# 15-FPGA-01b.net
KiCad netlist of a schematic drawn in Altium Designer
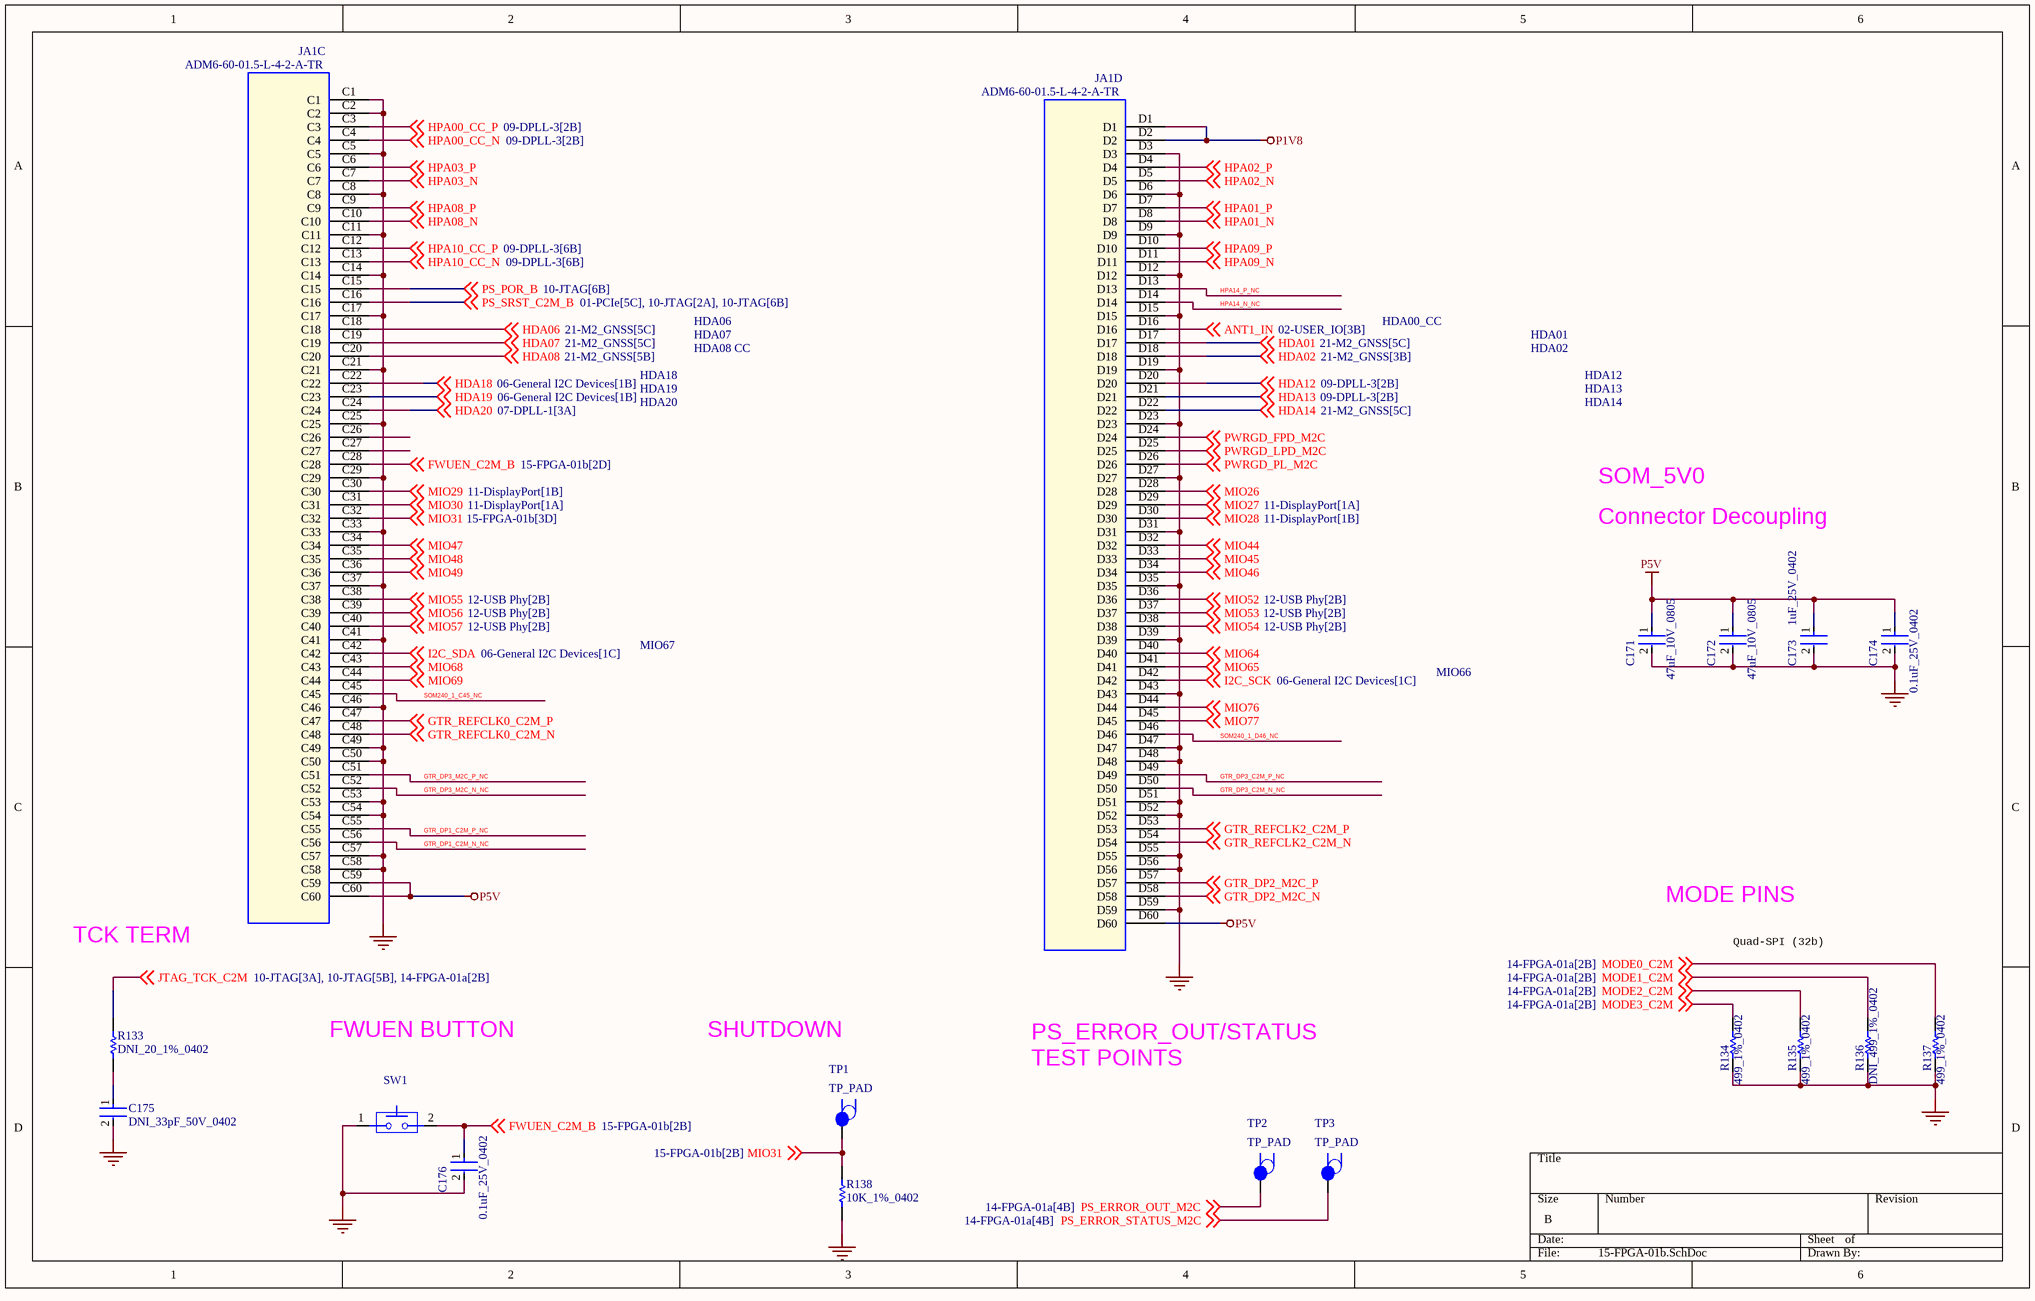
[diagram p0: 15-FPGA-01b.SchDoc]

(export (version "E")
  (design (tool "Eeschema 10.0.6"))
  (components
    (comp (ref "C171")
      (value "47uF_10V_0805")
      (footprint "FP-GRM21B-0_2-e0_2_0_7-IPC_A")
      (description "Chip Multilayer Ceramic Capacitors for General Purpose, 0805, 47uF, X5R, 15%, 20%, 10V")
      (fields (field (name "TOLERANCE") "20%") (field (name "VOLTAGE") "10V"))
      (libsource (lib "Altium Content Vault") (part "b4654b650e69147ec39a6b967a45e02"))
    )
    (comp (ref "C172")
      (value "47uF_10V_0805")
      (footprint "FP-GRM21B-0_2-e0_2_0_7-IPC_A")
      (description "Chip Multilayer Ceramic Capacitors for General Purpose, 0805, 47uF, X5R, 15%, 20%, 10V")
      (fields (field (name "TOLERANCE") "20%") (field (name "VOLTAGE") "10V"))
      (libsource (lib "Altium Content Vault") (part "b4654b650e69147ec39a6b967a45e02"))
    )
    (comp (ref "C173")
      (value "1uF_25V_0402")
      (footprint "FP-CL542-IPC_C")
      (description "Cap Ceramic 1uF 25V X5R ±10% SMD 0402 +85°C Paper T/R")
      (fields (field (name "TOLERANCE") "10%"))
      (libsource (lib "Altium Content Vault") (part "b4654b650e69147ec39a6b967a45e02"))
    )
    (comp (ref "C174")
      (value "0.1uF_25V_0402")
      (footprint "FP-0402-L_1_0_0_05-W_0_5-IPC_B")
      (description "None")
      (fields (field (name "TOLERANCE") "10%") (field (name "VOLTAGE") "25V"))
      (libsource (lib "Altium Content Vault") (part "b4654b650e69147ec39a6b967a45e02"))
    )
    (comp (ref "C175")
      (value "DNI_33pF_50V_0402")
      (footprint "FP-C1005-050-0_05-IPC_A")
      (description "Multilayer Ceramic Capacitors 33pF ±1% 50V C0G SMD 0402")
      (fields (field (name "TOLERANCE") "1%"))
      (libsource (lib "Altium Content Vault") (part "b4654b650e69147ec39a6b967a45e02"))
    )
    (comp (ref "C176")
      (value "0.1uF_25V_0402")
      (footprint "FP-0402-L_1_0_0_05-W_0_5-IPC_B")
      (description "None")
      (fields (field (name "TOLERANCE") "10%") (field (name "VOLTAGE") "25V"))
      (libsource (lib "Altium Content Vault") (part "b4654b650e69147ec39a6b967a45e02"))
    )
    (comp (ref "JA1")
      (value "ADM6-60-01.5-L-4-2-A-TR")
      (footprint "CON_SAMTEC_ADM6_60_4")
      (description "Conn Rcpt Male Vert 240 Pos 4x60 0.635mm P Black SMT")
      (fields (field (name "MANUFACTURER") "Samtec Inc.") (field (name "AGILE PART NUMBER") "CON-00383-01"))
      (libsource (lib "*") (part "SAMTEC-ADx6-60X4"))
    )
    (comp (ref "R133")
      (value "DNI_20_1%_0402")
      (footprint "RESC1005X40X25NL10T10")
      (fields
        (field (name "MANUFACTURER") "TE Connectivity / AMP")
        (field (name "PART NUMBER") "CRG0402F20R")
      )
      (libsource (lib "Altium Content Vault") (part "RES"))
    )
    (comp (ref "R134")
      (value "499_1%_0402")
      (footprint "RESC1005X40X25LL05T05")
      (fields (field (name "MANUFACTURER") "Vishay Dale") (field (name "PART NUMBER") "CRCW0402499RFKTD"))
      (libsource (lib "Altium Content Vault") (part "RES"))
    )
    (comp (ref "R135")
      (value "499_1%_0402")
      (footprint "RESC1005X40X25LL05T05")
      (fields (field (name "MANUFACTURER") "Vishay Dale") (field (name "PART NUMBER") "CRCW0402499RFKTD"))
      (libsource (lib "Altium Content Vault") (part "RES"))
    )
    (comp (ref "R136")
      (value "DNI_499_1%_0402")
      (footprint "RESC1005X40X25LL05T05")
      (fields (field (name "MANUFACTURER") "Vishay Dale") (field (name "PART NUMBER") "CRCW0402499RFKTD"))
      (libsource (lib "Altium Content Vault") (part "RES"))
    )
    (comp (ref "R137")
      (value "499_1%_0402")
      (footprint "RESC1005X40X25LL05T05")
      (fields (field (name "MANUFACTURER") "Vishay Dale") (field (name "PART NUMBER") "CRCW0402499RFKTD"))
      (libsource (lib "Altium Content Vault") (part "RES"))
    )
    (comp (ref "R138")
      (value "10K_1%_0402")
      (footprint "RESC1005X40X25ML05T05")
      (fields (field (name "PART NUMBER") "ERJ-2GEJ103X") (field (name "MANUFACTURER") "Panasonic"))
      (libsource (lib "Altium Content Vault") (part "RES"))
    )
    (comp (ref "SW1")
      (value "B3U-1000P")
      (footprint "SW_OMRON_2P")
      (description "Switch SPST-NO Mom 50mA 12V 1.6mm H 1.5Nw SMT IP40")
      (fields (field (name "MANUFACTURER") "OMRON") (field (name "AGILE PART NUMBER") "SWH-00003-01"))
      (libsource (lib "*") (part "BTN_MOMENT"))
    )
    (comp (ref "TP1")
      (value "TP_PAD")
      (footprint "TP_PAD")
      (description "TEST POINT 24mil SM pad")
      (fields (field (name "MANF") "DNP") (field (name "OWNER") "3709"))
      (libsource (lib "*") (part "TP"))
    )
    (comp (ref "TP2")
      (value "TP_PAD")
      (footprint "TP_PAD")
      (description "TEST POINT 24mil SM pad")
      (fields (field (name "MANF") "DNP") (field (name "OWNER") "3709"))
      (libsource (lib "*") (part "TP"))
    )
    (comp (ref "TP3")
      (value "TP_PAD")
      (footprint "TP_PAD")
      (description "TEST POINT 24mil SM pad")
      (fields (field (name "MANF") "DNP") (field (name "OWNER") "3709"))
      (libsource (lib "*") (part "TP"))
    )
  )
  (nets
    (net (code "1") (name "/GTR_DP1_C2M_N_NC") (class "Default")
      (node (ref "JA1") (pin "C56") (pinfunction "C56_C56") (pintype "passive"))
    )
    (net (code "2") (name "/GTR_DP1_C2M_P_NC") (class "Default")
      (node (ref "JA1") (pin "C55") (pinfunction "C55_C55") (pintype "passive"))
    )
    (net (code "3") (name "/GTR_DP3_C2M_N_NC") (class "Default")
      (node (ref "JA1") (pin "D50") (pinfunction "D50_D50") (pintype "passive"))
    )
    (net (code "4") (name "/GTR_DP3_C2M_P_NC") (class "Default")
      (node (ref "JA1") (pin "D49") (pinfunction "D49_D49") (pintype "passive"))
    )
    (net (code "5") (name "/GTR_DP3_M2C_N_NC") (class "Default")
      (node (ref "JA1") (pin "C52") (pinfunction "C52_C52") (pintype "passive"))
    )
    (net (code "6") (name "/GTR_DP3_M2C_P_NC") (class "Default")
      (node (ref "JA1") (pin "C51") (pinfunction "C51_C51") (pintype "passive"))
    )
    (net (code "7") (name "/HPA14_N_NC") (class "Default")
      (node (ref "JA1") (pin "D14") (pinfunction "D14_D14") (pintype "passive"))
    )
    (net (code "8") (name "/HPA14_P_NC") (class "Default")
      (node (ref "JA1") (pin "D13") (pinfunction "D13_D13") (pintype "passive"))
    )
    (net (code "9") (name "/SOM240_1_C45_NC") (class "Default")
      (node (ref "JA1") (pin "C45") (pinfunction "C45_C45") (pintype "passive"))
    )
    (net (code "10") (name "/SOM240_1_D46_NC") (class "Default")
      (node (ref "JA1") (pin "D46") (pinfunction "D46_D46") (pintype "passive"))
    )
    (net (code "11") (name "ANT1_IN") (class "Default")
      (node (ref "JA1") (pin "D16") (pinfunction "D16_D16") (pintype "passive"))
    )
    (net (code "12") (name "FWUEN_C2M_B") (class "Default")
      (node (ref "C176") (pin "1") (pinfunction "1_1") (pintype "passive"))
      (node (ref "JA1") (pin "C28") (pinfunction "C28_C28") (pintype "passive"))
      (node (ref "SW1") (pin "2") (pinfunction "SW2_2") (pintype "passive"))
    )
    (net (code "13") (name "GND") (class "Default")
      (node (ref "C171") (pin "2") (pinfunction "2_2") (pintype "passive"))
      (node (ref "C172") (pin "2") (pinfunction "2_2") (pintype "passive"))
      (node (ref "C173") (pin "2") (pinfunction "2_2") (pintype "passive"))
      (node (ref "C174") (pin "2") (pinfunction "2_2") (pintype "passive"))
      (node (ref "C175") (pin "2") (pinfunction "2_2") (pintype "passive"))
      (node (ref "C176") (pin "2") (pinfunction "2_2") (pintype "passive"))
      (node (ref "JA1") (pin "C1") (pinfunction "C1_C1") (pintype "passive"))
      (node (ref "JA1") (pin "C11") (pinfunction "C11_C11") (pintype "passive"))
      (node (ref "JA1") (pin "C14") (pinfunction "C14_C14") (pintype "passive"))
      (node (ref "JA1") (pin "C17") (pinfunction "C17_C17") (pintype "passive"))
      (node (ref "JA1") (pin "C2") (pinfunction "C2_C2") (pintype "passive"))
      (node (ref "JA1") (pin "C21") (pinfunction "C21_C21") (pintype "passive"))
      (node (ref "JA1") (pin "C25") (pinfunction "C25_C25") (pintype "passive"))
      (node (ref "JA1") (pin "C29") (pinfunction "C29_C29") (pintype "passive"))
      (node (ref "JA1") (pin "C33") (pinfunction "C33_C33") (pintype "passive"))
      (node (ref "JA1") (pin "C37") (pinfunction "C37_C37") (pintype "passive"))
      (node (ref "JA1") (pin "C41") (pinfunction "C41_C41") (pintype "passive"))
      (node (ref "JA1") (pin "C46") (pinfunction "C46_C46") (pintype "passive"))
      (node (ref "JA1") (pin "C49") (pinfunction "C49_C49") (pintype "passive"))
      (node (ref "JA1") (pin "C5") (pinfunction "C5_C5") (pintype "passive"))
      (node (ref "JA1") (pin "C50") (pinfunction "C50_C50") (pintype "passive"))
      (node (ref "JA1") (pin "C53") (pinfunction "C53_C53") (pintype "passive"))
      (node (ref "JA1") (pin "C54") (pinfunction "C54_C54") (pintype "passive"))
      (node (ref "JA1") (pin "C57") (pinfunction "C57_C57") (pintype "passive"))
      (node (ref "JA1") (pin "C58") (pinfunction "C58_C58") (pintype "passive"))
      (node (ref "JA1") (pin "C8") (pinfunction "C8_C8") (pintype "passive"))
      (node (ref "JA1") (pin "D12") (pinfunction "D12_D12") (pintype "passive"))
      (node (ref "JA1") (pin "D15") (pinfunction "D15_D15") (pintype "passive"))
      (node (ref "JA1") (pin "D19") (pinfunction "D19_D19") (pintype "passive"))
      (node (ref "JA1") (pin "D23") (pinfunction "D23_D23") (pintype "passive"))
      (node (ref "JA1") (pin "D27") (pinfunction "D27_D27") (pintype "passive"))
      (node (ref "JA1") (pin "D3") (pinfunction "D3_D3") (pintype "passive"))
      (node (ref "JA1") (pin "D31") (pinfunction "D31_D31") (pintype "passive"))
      (node (ref "JA1") (pin "D35") (pinfunction "D35_D35") (pintype "passive"))
      (node (ref "JA1") (pin "D39") (pinfunction "D39_D39") (pintype "passive"))
      (node (ref "JA1") (pin "D43") (pinfunction "D43_D43") (pintype "passive"))
      (node (ref "JA1") (pin "D47") (pinfunction "D47_D47") (pintype "passive"))
      (node (ref "JA1") (pin "D48") (pinfunction "D48_D48") (pintype "passive"))
      (node (ref "JA1") (pin "D51") (pinfunction "D51_D51") (pintype "passive"))
      (node (ref "JA1") (pin "D52") (pinfunction "D52_D52") (pintype "passive"))
      (node (ref "JA1") (pin "D55") (pinfunction "D55_D55") (pintype "passive"))
      (node (ref "JA1") (pin "D56") (pinfunction "D56_D56") (pintype "passive"))
      (node (ref "JA1") (pin "D59") (pinfunction "D59_D59") (pintype "passive"))
      (node (ref "JA1") (pin "D6") (pinfunction "D6_D6") (pintype "passive"))
      (node (ref "JA1") (pin "D9") (pinfunction "D9_D9") (pintype "passive"))
      (node (ref "R134") (pin "1") (pinfunction "1_1") (pintype "passive"))
      (node (ref "R135") (pin "1") (pinfunction "1_1") (pintype "passive"))
      (node (ref "R136") (pin "1") (pinfunction "1_1") (pintype "passive"))
      (node (ref "R137") (pin "1") (pinfunction "1_1") (pintype "passive"))
      (node (ref "R138") (pin "1") (pinfunction "1_1") (pintype "passive"))
      (node (ref "SW1") (pin "1") (pinfunction "SW1_1") (pintype "passive"))
    )
    (net (code "14") (name "GTR_DP2_M2C_N") (class "Default")
      (node (ref "JA1") (pin "D58") (pinfunction "D58_D58") (pintype "passive"))
    )
    (net (code "15") (name "GTR_DP2_M2C_P") (class "Default")
      (node (ref "JA1") (pin "D57") (pinfunction "D57_D57") (pintype "passive"))
    )
    (net (code "16") (name "GTR_REFCLK0_C2M_N") (class "Default")
      (node (ref "JA1") (pin "C48") (pinfunction "C48_C48") (pintype "passive"))
    )
    (net (code "17") (name "GTR_REFCLK0_C2M_P") (class "Default")
      (node (ref "JA1") (pin "C47") (pinfunction "C47_C47") (pintype "passive"))
    )
    (net (code "18") (name "GTR_REFCLK2_C2M_N") (class "Default")
      (node (ref "JA1") (pin "D54") (pinfunction "D54_D54") (pintype "passive"))
    )
    (net (code "19") (name "GTR_REFCLK2_C2M_P") (class "Default")
      (node (ref "JA1") (pin "D53") (pinfunction "D53_D53") (pintype "passive"))
    )
    (net (code "20") (name "HDA01") (class "Default")
      (node (ref "JA1") (pin "D17") (pinfunction "D17_D17") (pintype "passive"))
    )
    (net (code "21") (name "HDA02") (class "Default")
      (node (ref "JA1") (pin "D18") (pinfunction "D18_D18") (pintype "passive"))
    )
    (net (code "22") (name "HDA06") (class "Default")
      (node (ref "JA1") (pin "C18") (pinfunction "C18_C18") (pintype "passive"))
    )
    (net (code "23") (name "HDA07") (class "Default")
      (node (ref "JA1") (pin "C19") (pinfunction "C19_C19") (pintype "passive"))
    )
    (net (code "24") (name "HDA08") (class "Default")
      (node (ref "JA1") (pin "C20") (pinfunction "C20_C20") (pintype "passive"))
    )
    (net (code "25") (name "HDA12") (class "Default")
      (node (ref "JA1") (pin "D20") (pinfunction "D20_D20") (pintype "passive"))
    )
    (net (code "26") (name "HDA13") (class "Default")
      (node (ref "JA1") (pin "D21") (pinfunction "D21_D21") (pintype "passive"))
    )
    (net (code "27") (name "HDA14") (class "Default")
      (node (ref "JA1") (pin "D22") (pinfunction "D22_D22") (pintype "passive"))
    )
    (net (code "28") (name "HDA18") (class "Default")
      (node (ref "JA1") (pin "C22") (pinfunction "C22_C22") (pintype "passive"))
    )
    (net (code "29") (name "HDA19") (class "Default")
      (node (ref "JA1") (pin "C23") (pinfunction "C23_C23") (pintype "passive"))
    )
    (net (code "30") (name "HDA20") (class "Default")
      (node (ref "JA1") (pin "C24") (pinfunction "C24_C24") (pintype "passive"))
    )
    (net (code "31") (name "HPA00_CC_N") (class "Default")
      (node (ref "JA1") (pin "C4") (pinfunction "C4_C4") (pintype "passive"))
    )
    (net (code "32") (name "HPA00_CC_P") (class "Default")
      (node (ref "JA1") (pin "C3") (pinfunction "C3_C3") (pintype "passive"))
    )
    (net (code "33") (name "HPA01_N") (class "Default")
      (node (ref "JA1") (pin "D8") (pinfunction "D8_D8") (pintype "passive"))
    )
    (net (code "34") (name "HPA01_P") (class "Default")
      (node (ref "JA1") (pin "D7") (pinfunction "D7_D7") (pintype "passive"))
    )
    (net (code "35") (name "HPA02_N") (class "Default")
      (node (ref "JA1") (pin "D5") (pinfunction "D5_D5") (pintype "passive"))
    )
    (net (code "36") (name "HPA02_P") (class "Default")
      (node (ref "JA1") (pin "D4") (pinfunction "D4_D4") (pintype "passive"))
    )
    (net (code "37") (name "HPA03_N") (class "Default")
      (node (ref "JA1") (pin "C7") (pinfunction "C7_C7") (pintype "passive"))
    )
    (net (code "38") (name "HPA03_P") (class "Default")
      (node (ref "JA1") (pin "C6") (pinfunction "C6_C6") (pintype "passive"))
    )
    (net (code "39") (name "HPA08_N") (class "Default")
      (node (ref "JA1") (pin "C10") (pinfunction "C10_C10") (pintype "passive"))
    )
    (net (code "40") (name "HPA08_P") (class "Default")
      (node (ref "JA1") (pin "C9") (pinfunction "C9_C9") (pintype "passive"))
    )
    (net (code "41") (name "HPA09_N") (class "Default")
      (node (ref "JA1") (pin "D11") (pinfunction "D11_D11") (pintype "passive"))
    )
    (net (code "42") (name "HPA09_P") (class "Default")
      (node (ref "JA1") (pin "D10") (pinfunction "D10_D10") (pintype "passive"))
    )
    (net (code "43") (name "HPA10_CC_N") (class "Default")
      (node (ref "JA1") (pin "C13") (pinfunction "C13_C13") (pintype "passive"))
    )
    (net (code "44") (name "HPA10_CC_P") (class "Default")
      (node (ref "JA1") (pin "C12") (pinfunction "C12_C12") (pintype "passive"))
    )
    (net (code "45") (name "I2C_SCK") (class "Default")
      (node (ref "JA1") (pin "D42") (pinfunction "D42_D42") (pintype "passive"))
    )
    (net (code "46") (name "I2C_SDA") (class "Default")
      (node (ref "JA1") (pin "C42") (pinfunction "C42_C42") (pintype "passive"))
    )
    (net (code "47") (name "JTAG_TCK_C2M") (class "Default")
      (node (ref "R133") (pin "2") (pinfunction "2_2") (pintype "passive"))
    )
    (net (code "48") (name "MIO26") (class "Default")
      (node (ref "JA1") (pin "D28") (pinfunction "D28_D28") (pintype "passive"))
    )
    (net (code "49") (name "MIO27") (class "Default")
      (node (ref "JA1") (pin "D29") (pinfunction "D29_D29") (pintype "passive"))
    )
    (net (code "50") (name "MIO28") (class "Default")
      (node (ref "JA1") (pin "D30") (pinfunction "D30_D30") (pintype "passive"))
    )
    (net (code "51") (name "MIO29") (class "Default")
      (node (ref "JA1") (pin "C30") (pinfunction "C30_C30") (pintype "passive"))
    )
    (net (code "52") (name "MIO30") (class "Default")
      (node (ref "JA1") (pin "C31") (pinfunction "C31_C31") (pintype "passive"))
    )
    (net (code "53") (name "MIO31") (class "Default")
      (node (ref "JA1") (pin "C32") (pinfunction "C32_C32") (pintype "passive"))
      (node (ref "R138") (pin "2") (pinfunction "2_2") (pintype "passive"))
      (node (ref "TP1") (pin "1") (pinfunction "TP_1") (pintype "passive"))
    )
    (net (code "54") (name "MIO44") (class "Default")
      (node (ref "JA1") (pin "D32") (pinfunction "D32_D32") (pintype "passive"))
    )
    (net (code "55") (name "MIO45") (class "Default")
      (node (ref "JA1") (pin "D33") (pinfunction "D33_D33") (pintype "passive"))
    )
    (net (code "56") (name "MIO46") (class "Default")
      (node (ref "JA1") (pin "D34") (pinfunction "D34_D34") (pintype "passive"))
    )
    (net (code "57") (name "MIO47") (class "Default")
      (node (ref "JA1") (pin "C34") (pinfunction "C34_C34") (pintype "passive"))
    )
    (net (code "58") (name "MIO48") (class "Default")
      (node (ref "JA1") (pin "C35") (pinfunction "C35_C35") (pintype "passive"))
    )
    (net (code "59") (name "MIO49") (class "Default")
      (node (ref "JA1") (pin "C36") (pinfunction "C36_C36") (pintype "passive"))
    )
    (net (code "60") (name "MIO52") (class "Default")
      (node (ref "JA1") (pin "D36") (pinfunction "D36_D36") (pintype "passive"))
    )
    (net (code "61") (name "MIO53") (class "Default")
      (node (ref "JA1") (pin "D37") (pinfunction "D37_D37") (pintype "passive"))
    )
    (net (code "62") (name "MIO54") (class "Default")
      (node (ref "JA1") (pin "D38") (pinfunction "D38_D38") (pintype "passive"))
    )
    (net (code "63") (name "MIO55") (class "Default")
      (node (ref "JA1") (pin "C38") (pinfunction "C38_C38") (pintype "passive"))
    )
    (net (code "64") (name "MIO56") (class "Default")
      (node (ref "JA1") (pin "C39") (pinfunction "C39_C39") (pintype "passive"))
    )
    (net (code "65") (name "MIO57") (class "Default")
      (node (ref "JA1") (pin "C40") (pinfunction "C40_C40") (pintype "passive"))
    )
    (net (code "66") (name "MIO64") (class "Default")
      (node (ref "JA1") (pin "D40") (pinfunction "D40_D40") (pintype "passive"))
    )
    (net (code "67") (name "MIO65") (class "Default")
      (node (ref "JA1") (pin "D41") (pinfunction "D41_D41") (pintype "passive"))
    )
    (net (code "68") (name "MIO68") (class "Default")
      (node (ref "JA1") (pin "C43") (pinfunction "C43_C43") (pintype "passive"))
    )
    (net (code "69") (name "MIO69") (class "Default")
      (node (ref "JA1") (pin "C44") (pinfunction "C44_C44") (pintype "passive"))
    )
    (net (code "70") (name "MIO76") (class "Default")
      (node (ref "JA1") (pin "D44") (pinfunction "D44_D44") (pintype "passive"))
    )
    (net (code "71") (name "MIO77") (class "Default")
      (node (ref "JA1") (pin "D45") (pinfunction "D45_D45") (pintype "passive"))
    )
    (net (code "72") (name "MODE0_C2M") (class "Default")
      (node (ref "R137") (pin "2") (pinfunction "2_2") (pintype "passive"))
    )
    (net (code "73") (name "MODE1_C2M") (class "Default")
      (node (ref "R136") (pin "2") (pinfunction "2_2") (pintype "passive"))
    )
    (net (code "74") (name "MODE2_C2M") (class "Default")
      (node (ref "R135") (pin "2") (pinfunction "2_2") (pintype "passive"))
    )
    (net (code "75") (name "MODE3_C2M") (class "Default")
      (node (ref "R134") (pin "2") (pinfunction "2_2") (pintype "passive"))
    )
    (net (code "76") (name "Net-(C175-Pad1)") (class "Default")
      (node (ref "C175") (pin "1") (pinfunction "1_1") (pintype "passive"))
      (node (ref "R133") (pin "1") (pinfunction "1_1") (pintype "passive"))
    )
    (net (code "77") (name "P1V8") (class "Default")
      (node (ref "JA1") (pin "D1") (pinfunction "D1_D1") (pintype "passive"))
      (node (ref "JA1") (pin "D2") (pinfunction "D2_D2") (pintype "passive"))
    )
    (net (code "78") (name "P5V") (class "Default")
      (node (ref "C171") (pin "1") (pinfunction "1_1") (pintype "passive"))
      (node (ref "C172") (pin "1") (pinfunction "1_1") (pintype "passive"))
      (node (ref "C173") (pin "1") (pinfunction "1_1") (pintype "passive"))
      (node (ref "C174") (pin "1") (pinfunction "1_1") (pintype "passive"))
      (node (ref "JA1") (pin "C59") (pinfunction "C59_C59") (pintype "passive"))
      (node (ref "JA1") (pin "C60") (pinfunction "C60_C60") (pintype "passive"))
      (node (ref "JA1") (pin "D60") (pinfunction "D60_D60") (pintype "passive"))
    )
    (net (code "79") (name "PS_ERROR_OUT_M2C") (class "Default")
      (node (ref "TP2") (pin "1") (pinfunction "TP_1") (pintype "passive"))
    )
    (net (code "80") (name "PS_ERROR_STATUS_M2C") (class "Default")
      (node (ref "TP3") (pin "1") (pinfunction "TP_1") (pintype "passive"))
    )
    (net (code "81") (name "PS_POR_B") (class "Default")
      (node (ref "JA1") (pin "C15") (pinfunction "C15_C15") (pintype "passive"))
    )
    (net (code "82") (name "PS_SRST_C2M_B") (class "Default")
      (node (ref "JA1") (pin "C16") (pinfunction "C16_C16") (pintype "passive"))
    )
    (net (code "83") (name "PWRGD_FPD_M2C") (class "Default")
      (node (ref "JA1") (pin "D24") (pinfunction "D24_D24") (pintype "passive"))
    )
    (net (code "84") (name "PWRGD_LPD_M2C") (class "Default")
      (node (ref "JA1") (pin "D25") (pinfunction "D25_D25") (pintype "passive"))
    )
    (net (code "85") (name "PWRGD_PL_M2C") (class "Default")
      (node (ref "JA1") (pin "D26") (pinfunction "D26_D26") (pintype "passive"))
    )
    (net (code "86") (name "unconnected-(JA1-PadC26)") (class "Default")
      (node (ref "JA1") (pin "C26") (pinfunction "C26_C26") (pintype "passive"))
    )
    (net (code "87") (name "unconnected-(JA1-PadC27)") (class "Default")
      (node (ref "JA1") (pin "C27") (pinfunction "C27_C27") (pintype "passive"))
    )
  )
)
